# 2018_ACT_EXPANDER_PUMP_EV.net
KiCad netlist of a schematic drawn in Altium Designer
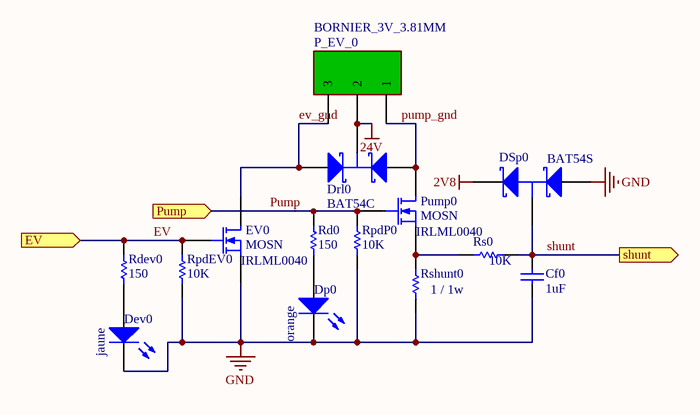
[diagram p0: 2018_ACT_EXPANDER_PUMP+EV.SchDoc]

(export (version "E")
  (design (tool "Eeschema 10.0.6"))
  (components
    (comp (ref "Cf0")
      (value "1uF")
      (footprint "C0805_N")
      (description "Capacitor")
      (fields (field (name "PUBLISHER") "Altium Limited"))
      (libsource (lib "_ROBOT") (part "Condensateur"))
    )
    (comp (ref "Dev0")
      (value "jaune")
      (footprint "LED_0805")
      (description "Typical LED")
      (fields (field (name "PUBLISHER") "Altium Limited"))
      (libsource (lib "_ROBOT") (part "LED"))
    )
    (comp (ref "Dp0")
      (value "orange")
      (footprint "LED_0805")
      (description "Typical LED")
      (fields (field (name "PUBLISHER") "Altium Limited"))
      (libsource (lib "_ROBOT") (part "LED"))
    )
    (comp (ref "Drl0")
      (value "BAT54C")
      (footprint "SOT23-3N")
      (description "DIODE SCHOTTKY DOUBLE")
      (fields (field (name "MANUFACTURER") "ZETEX"))
      (libsource (lib "_ROBOT") (part "Diode Shottky double BAT54C"))
    )
    (comp (ref "DSp0")
      (value "BAT54S")
      (footprint "SOT23-3N")
      (description "DIODE SCHOTTKY DOUBLE")
      (fields (field (name "MANUFACTURER") "ZETEX"))
      (libsource (lib "_ROBOT") (part "Diode Shottky double BAT54S"))
    )
    (comp (ref "EV0")
      (value "MOSN")
      (footprint "SOT23-3N")
      (description "N-Channel MOSFET")
      (fields (field (name "ALTIUM_UNNAMED_1") "IRLML0040") (field (name "PUBLISHER") "Altium Limited"))
      (libsource (lib "_ROBOT") (part "Transistor MOSFET-N"))
    )
    (comp (ref "Pump0")
      (value "MOSN")
      (footprint "SOT23-3N")
      (description "N-Channel MOSFET")
      (fields (field (name "ALTIUM_UNNAMED_1") "IRLML0040") (field (name "PUBLISHER") "Altium Limited"))
      (libsource (lib "_ROBOT") (part "Transistor MOSFET-N"))
    )
    (comp (ref "P_EV_0")
      (value "BORNIER_3V_3.81MM")
      (footprint "BORNIER_3V_3.81MM")
      (libsource (lib "Connecteur") (part "BORNIER_3V_3.81MM"))
    )
    (comp (ref "Rd0")
      (value "150")
      (footprint "R1206_N")
      (description "Resistor")
      (fields (field (name "PUBLISHER") "Altium Limited"))
      (libsource (lib "_ROBOT") (part "Resistor"))
    )
    (comp (ref "Rdev0")
      (value "150")
      (footprint "R1206_N")
      (description "Resistor")
      (fields (field (name "PUBLISHER") "Altium Limited"))
      (libsource (lib "_ROBOT") (part "Resistor"))
    )
    (comp (ref "RpdEV0")
      (value "10K")
      (footprint "R1206_N")
      (description "Resistor")
      (fields (field (name "PUBLISHER") "Altium Limited"))
      (libsource (lib "_ROBOT") (part "Resistor"))
    )
    (comp (ref "RpdP0")
      (value "10K")
      (footprint "R1206_N")
      (description "Resistor")
      (fields (field (name "PUBLISHER") "Altium Limited"))
      (libsource (lib "_ROBOT") (part "Resistor"))
    )
    (comp (ref "Rs0")
      (value "10K")
      (footprint "R1206_N")
      (description "Resistor")
      (fields (field (name "PUBLISHER") "Altium Limited"))
      (libsource (lib "_ROBOT") (part "Resistor"))
    )
    (comp (ref "Rshunt0")
      (value "1 / 1w")
      (footprint "INDUCTANCE_CMS_1812")
      (description "Resistor")
      (fields (field (name "PUBLISHER") "Altium Limited"))
      (libsource (lib "_ROBOT") (part "Resistor"))
    )
  )
  (nets
    (net (code "1") (name "/EV") (class "Default")
      (node (ref "EV0") (pin "1") (pinfunction "G_1") (pintype "passive"))
      (node (ref "Rdev0") (pin "2") (pinfunction "2_2") (pintype "passive"))
      (node (ref "RpdEV0") (pin "2") (pinfunction "2_2") (pintype "passive"))
    )
    (net (code "2") (name "/Pump") (class "Default")
      (node (ref "Pump0") (pin "1") (pinfunction "G_1") (pintype "passive"))
      (node (ref "Rd0") (pin "2") (pinfunction "2_2") (pintype "passive"))
      (node (ref "RpdP0") (pin "2") (pinfunction "2_2") (pintype "passive"))
    )
    (net (code "3") (name "/ev_gnd") (class "Default")
      (node (ref "Drl0") (pin "1") (pinfunction "A1_1") (pintype "passive"))
      (node (ref "EV0") (pin "3") (pinfunction "D_3") (pintype "passive"))
      (node (ref "P_EV_0") (pin "3") (pinfunction "3_3") (pintype "passive"))
    )
    (net (code "4") (name "/pump_gnd") (class "Default")
      (node (ref "Drl0") (pin "2") (pinfunction "A2_2") (pintype "passive"))
      (node (ref "P_EV_0") (pin "1") (pinfunction "1_1") (pintype "passive"))
      (node (ref "Pump0") (pin "3") (pinfunction "D_3") (pintype "passive"))
    )
    (net (code "5") (name "/shunt") (class "Default")
      (node (ref "Cf0") (pin "2") (pinfunction "2_2") (pintype "passive"))
      (node (ref "DSp0") (pin "3") (pinfunction "C_3") (pintype "passive"))
      (node (ref "Rs0") (pin "2") (pinfunction "2_2") (pintype "passive"))
    )
    (net (code "6") (name "2V8") (class "Default")
      (node (ref "DSp0") (pin "2") (pinfunction "K_2") (pintype "passive"))
    )
    (net (code "7") (name "24V") (class "Default")
      (node (ref "Drl0") (pin "3") (pinfunction "K_3") (pintype "passive"))
      (node (ref "P_EV_0") (pin "2") (pinfunction "2_2") (pintype "passive"))
    )
    (net (code "8") (name "GND") (class "Default")
      (node (ref "Cf0") (pin "1") (pinfunction "1_1") (pintype "passive"))
      (node (ref "DSp0") (pin "1") (pinfunction "A_1") (pintype "passive"))
      (node (ref "Dev0") (pin "2") (pinfunction "K_2") (pintype "passive"))
      (node (ref "Dp0") (pin "2") (pinfunction "K_2") (pintype "passive"))
      (node (ref "EV0") (pin "2") (pinfunction "S_2") (pintype "passive"))
      (node (ref "RpdEV0") (pin "1") (pinfunction "1_1") (pintype "passive"))
      (node (ref "RpdP0") (pin "1") (pinfunction "1_1") (pintype "passive"))
      (node (ref "Rshunt0") (pin "1") (pinfunction "1_1") (pintype "passive"))
    )
    (net (code "9") (name "Net-(Dev0-A)") (class "Default")
      (node (ref "Dev0") (pin "1") (pinfunction "A_1") (pintype "passive"))
      (node (ref "Rdev0") (pin "1") (pinfunction "1_1") (pintype "passive"))
    )
    (net (code "10") (name "Net-(Dp0-A)") (class "Default")
      (node (ref "Dp0") (pin "1") (pinfunction "A_1") (pintype "passive"))
      (node (ref "Rd0") (pin "1") (pinfunction "1_1") (pintype "passive"))
    )
    (net (code "11") (name "Net-(Pump0-S)") (class "Default")
      (node (ref "Pump0") (pin "2") (pinfunction "S_2") (pintype "passive"))
      (node (ref "Rs0") (pin "1") (pinfunction "1_1") (pintype "passive"))
      (node (ref "Rshunt0") (pin "2") (pinfunction "2_2") (pintype "passive"))
    )
  )
)
